# addonv2.net
KiCad netlist of a schematic drawn in EAGLE
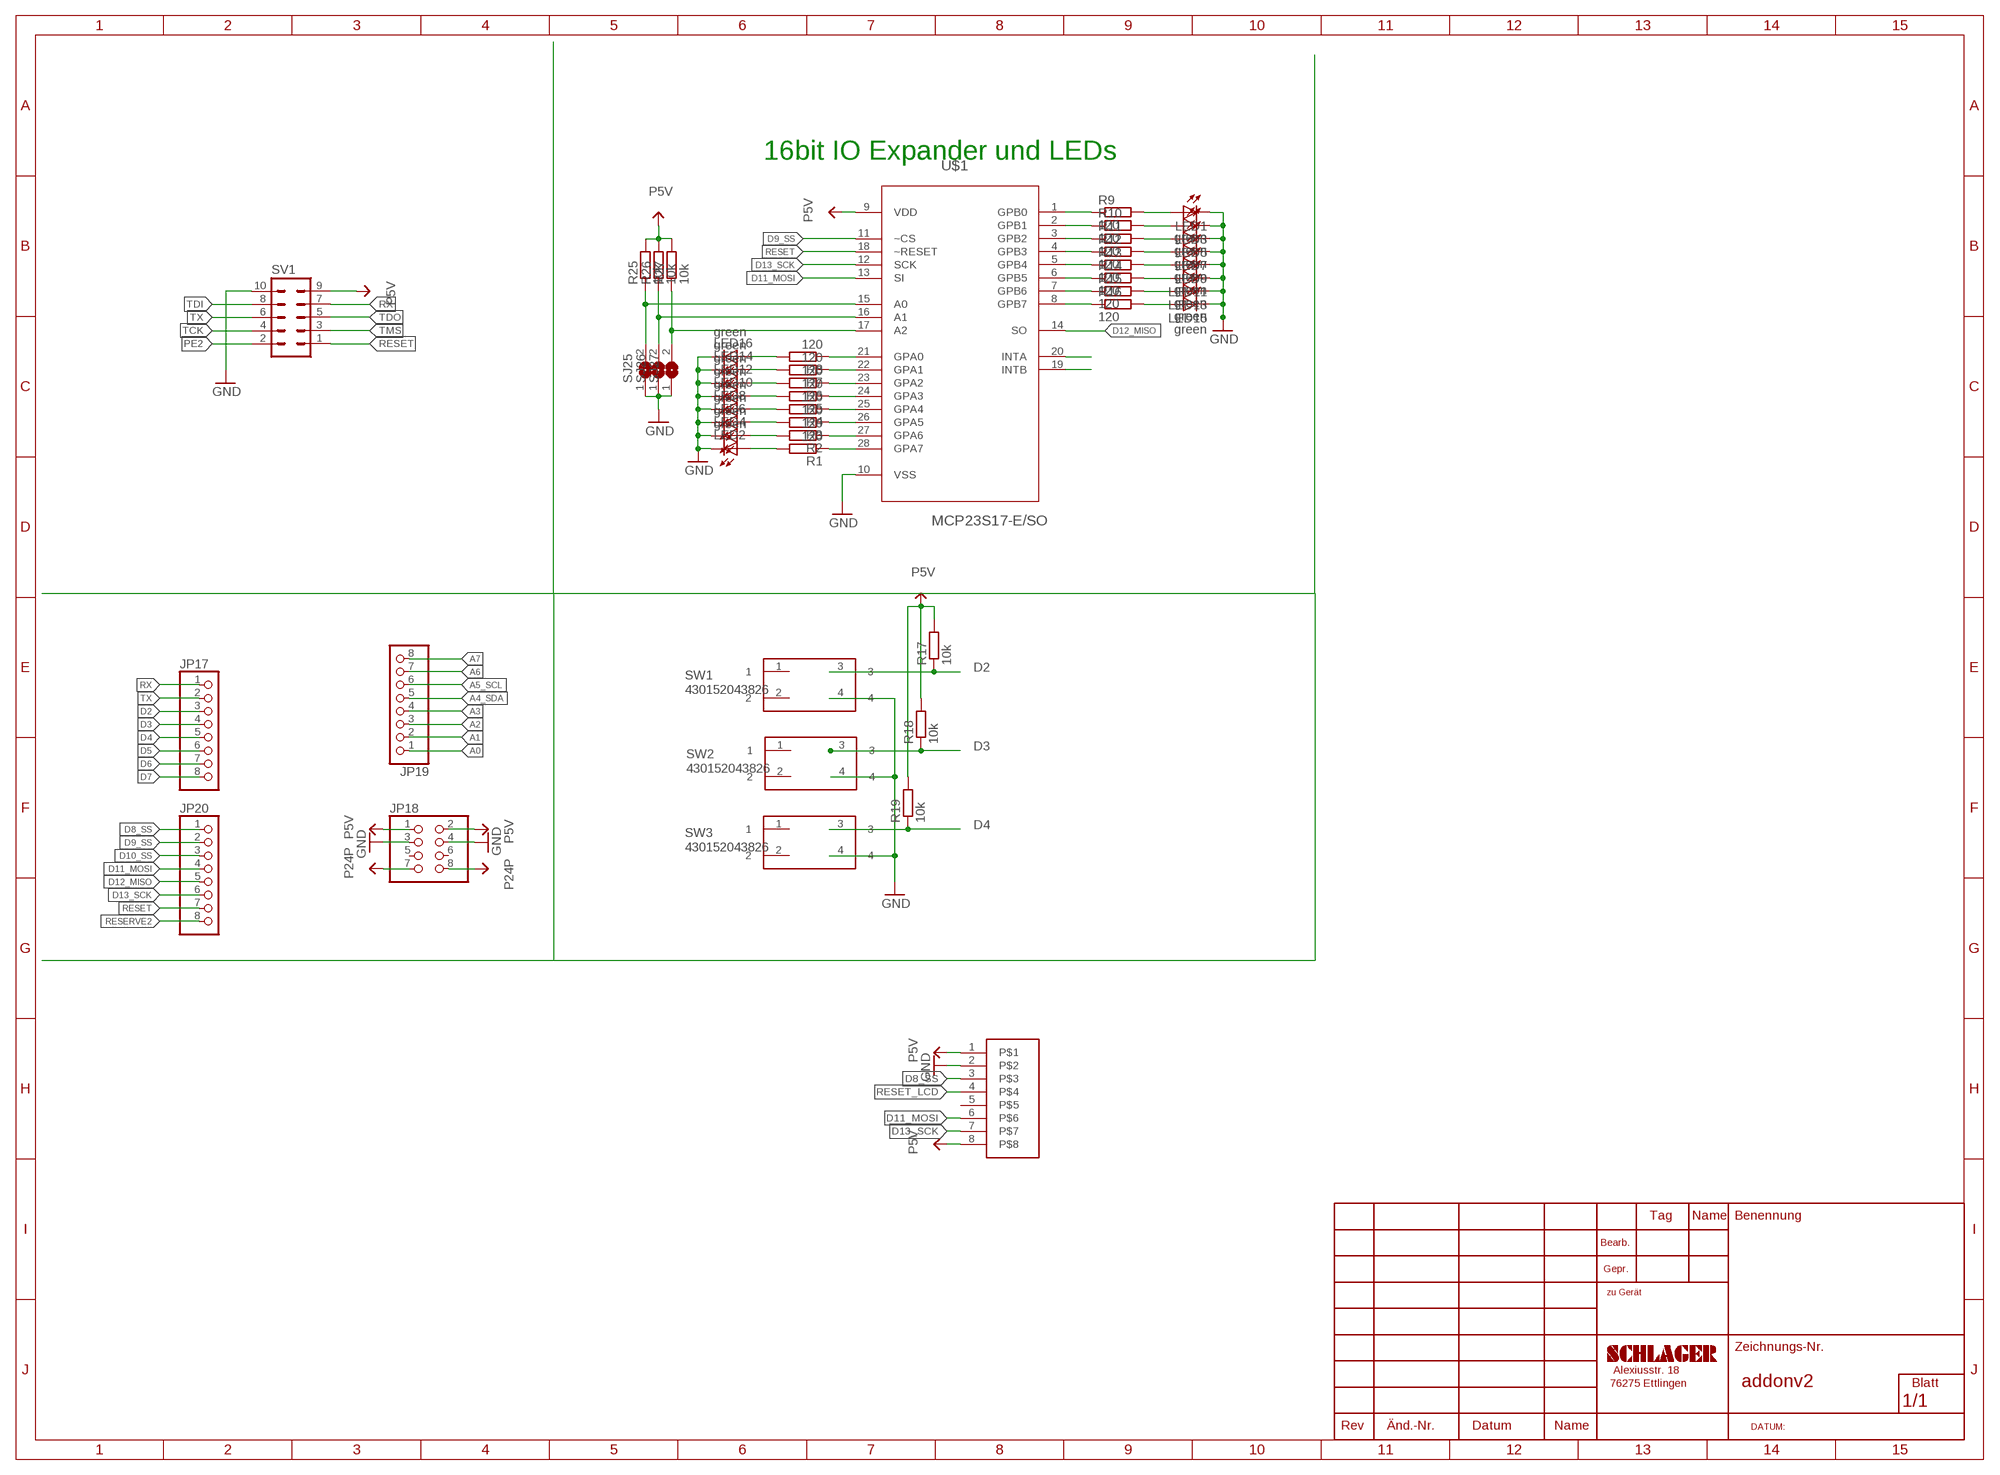
[diagram p0: schematic, sheet 1]

(export (version "E")
  (design (tool "Eeschema 10.0.6"))
  (components
    (comp (ref "JP17")
      (value "PINHD-1X8")
      (footprint "eagle-import:1X08")
      (libsource (lib "eagle-import") (part "PINHD-1X8"))
    )
    (comp (ref "JP18")
      (value "PINHD-2X4")
      (footprint "eagle-import:2X04")
      (libsource (lib "eagle-import") (part "PINHD-2X4"))
    )
    (comp (ref "JP19")
      (value "PINHD-1X8")
      (footprint "eagle-import:1X08")
      (libsource (lib "eagle-import") (part "PINHD-1X8"))
    )
    (comp (ref "JP20")
      (value "PINHD-1X8")
      (footprint "eagle-import:1X08")
      (libsource (lib "eagle-import") (part "PINHD-1X8"))
    )
    (comp (ref "LED1")
      (value "green")
      (footprint "eagle-import:CHIPLED_0805")
      (libsource (lib "eagle-import") (part "LEDCHIPLED_0805"))
    )
    (comp (ref "LED2")
      (value "green")
      (footprint "eagle-import:CHIPLED_0805")
      (libsource (lib "eagle-import") (part "LEDCHIPLED_0805"))
    )
    (comp (ref "LED3")
      (value "green")
      (footprint "eagle-import:CHIPLED_0805")
      (libsource (lib "eagle-import") (part "LEDCHIPLED_0805"))
    )
    (comp (ref "LED4")
      (value "green")
      (footprint "eagle-import:CHIPLED_0805")
      (libsource (lib "eagle-import") (part "LEDCHIPLED_0805"))
    )
    (comp (ref "LED5")
      (value "green")
      (footprint "eagle-import:CHIPLED_0805")
      (libsource (lib "eagle-import") (part "LEDCHIPLED_0805"))
    )
    (comp (ref "LED6")
      (value "green")
      (footprint "eagle-import:CHIPLED_0805")
      (libsource (lib "eagle-import") (part "LEDCHIPLED_0805"))
    )
    (comp (ref "LED7")
      (value "green")
      (footprint "eagle-import:CHIPLED_0805")
      (libsource (lib "eagle-import") (part "LEDCHIPLED_0805"))
    )
    (comp (ref "LED8")
      (value "green")
      (footprint "eagle-import:CHIPLED_0805")
      (libsource (lib "eagle-import") (part "LEDCHIPLED_0805"))
    )
    (comp (ref "LED9")
      (value "green")
      (footprint "eagle-import:CHIPLED_0805")
      (libsource (lib "eagle-import") (part "LEDCHIPLED_0805"))
    )
    (comp (ref "LED10")
      (value "green")
      (footprint "eagle-import:CHIPLED_0805")
      (libsource (lib "eagle-import") (part "LEDCHIPLED_0805"))
    )
    (comp (ref "LED11")
      (value "green")
      (footprint "eagle-import:CHIPLED_0805")
      (libsource (lib "eagle-import") (part "LEDCHIPLED_0805"))
    )
    (comp (ref "LED12")
      (value "green")
      (footprint "eagle-import:CHIPLED_0805")
      (libsource (lib "eagle-import") (part "LEDCHIPLED_0805"))
    )
    (comp (ref "LED13")
      (value "green")
      (footprint "eagle-import:CHIPLED_0805")
      (libsource (lib "eagle-import") (part "LEDCHIPLED_0805"))
    )
    (comp (ref "LED14")
      (value "green")
      (footprint "eagle-import:CHIPLED_0805")
      (libsource (lib "eagle-import") (part "LEDCHIPLED_0805"))
    )
    (comp (ref "LED15")
      (value "green")
      (footprint "eagle-import:CHIPLED_0805")
      (libsource (lib "eagle-import") (part "LEDCHIPLED_0805"))
    )
    (comp (ref "LED16")
      (value "green")
      (footprint "eagle-import:CHIPLED_0805")
      (libsource (lib "eagle-import") (part "LEDCHIPLED_0805"))
    )
    (comp (ref "R1")
      (value "120")
      (footprint "eagle-import:R0805")
      (libsource (lib "eagle-import") (part "R-EU_R0805"))
    )
    (comp (ref "R2")
      (value "120")
      (footprint "eagle-import:R0805")
      (libsource (lib "eagle-import") (part "R-EU_R0805"))
    )
    (comp (ref "R3")
      (value "120")
      (footprint "eagle-import:R0805")
      (libsource (lib "eagle-import") (part "R-EU_R0805"))
    )
    (comp (ref "R4")
      (value "120")
      (footprint "eagle-import:R0805")
      (libsource (lib "eagle-import") (part "R-EU_R0805"))
    )
    (comp (ref "R5")
      (value "120")
      (footprint "eagle-import:R0805")
      (libsource (lib "eagle-import") (part "R-EU_R0805"))
    )
    (comp (ref "R6")
      (value "120")
      (footprint "eagle-import:R0805")
      (libsource (lib "eagle-import") (part "R-EU_R0805"))
    )
    (comp (ref "R7")
      (value "120")
      (footprint "eagle-import:R0805")
      (libsource (lib "eagle-import") (part "R-EU_R0805"))
    )
    (comp (ref "R8")
      (value "120")
      (footprint "eagle-import:R0805")
      (libsource (lib "eagle-import") (part "R-EU_R0805"))
    )
    (comp (ref "R9")
      (value "120")
      (footprint "eagle-import:R0805")
      (libsource (lib "eagle-import") (part "R-EU_R0805"))
    )
    (comp (ref "R10")
      (value "120")
      (footprint "eagle-import:R0805")
      (libsource (lib "eagle-import") (part "R-EU_R0805"))
    )
    (comp (ref "R11")
      (value "120")
      (footprint "eagle-import:R0805")
      (libsource (lib "eagle-import") (part "R-EU_R0805"))
    )
    (comp (ref "R12")
      (value "120")
      (footprint "eagle-import:R0805")
      (libsource (lib "eagle-import") (part "R-EU_R0805"))
    )
    (comp (ref "R13")
      (value "120")
      (footprint "eagle-import:R0805")
      (libsource (lib "eagle-import") (part "R-EU_R0805"))
    )
    (comp (ref "R14")
      (value "120")
      (footprint "eagle-import:R0805")
      (libsource (lib "eagle-import") (part "R-EU_R0805"))
    )
    (comp (ref "R15")
      (value "120")
      (footprint "eagle-import:R0805")
      (libsource (lib "eagle-import") (part "R-EU_R0805"))
    )
    (comp (ref "R16")
      (value "120")
      (footprint "eagle-import:R0805")
      (libsource (lib "eagle-import") (part "R-EU_R0805"))
    )
    (comp (ref "R17")
      (value "10k")
      (footprint "eagle-import:R0805")
      (libsource (lib "eagle-import") (part "R-EU_R0805"))
    )
    (comp (ref "R18")
      (value "10k")
      (footprint "eagle-import:R0805")
      (libsource (lib "eagle-import") (part "R-EU_R0805"))
    )
    (comp (ref "R19")
      (value "10k")
      (footprint "eagle-import:R0805")
      (libsource (lib "eagle-import") (part "R-EU_R0805"))
    )
    (comp (ref "R25")
      (value "10k")
      (footprint "eagle-import:R0805")
      (libsource (lib "eagle-import") (part "R-EU_R0805"))
    )
    (comp (ref "R26")
      (value "10k")
      (footprint "eagle-import:R0805")
      (libsource (lib "eagle-import") (part "R-EU_R0805"))
    )
    (comp (ref "R27")
      (value "10k")
      (footprint "eagle-import:R0805")
      (libsource (lib "eagle-import") (part "R-EU_R0805"))
    )
    (comp (ref "SJ25")
      (value "SJN")
      (footprint "eagle-import:SJ")
      (libsource (lib "eagle-import") (part "SJN"))
    )
    (comp (ref "SJ26")
      (value "SJN")
      (footprint "eagle-import:SJ")
      (libsource (lib "eagle-import") (part "SJN"))
    )
    (comp (ref "SJ27")
      (value "SJN")
      (footprint "eagle-import:SJ")
      (libsource (lib "eagle-import") (part "SJN"))
    )
    (comp (ref "SV1")
      (value "ML10L")
      (footprint "eagle-import:ML10L")
      (libsource (lib "eagle-import") (part "ML10L"))
    )
    (comp (ref "SW1")
      (value "430152043826")
      (footprint "eagle-import:430152043826")
      (libsource (lib "eagle-import") (part "430152043826"))
    )
    (comp (ref "SW2")
      (value "430152043826")
      (footprint "eagle-import:430152043826")
      (libsource (lib "eagle-import") (part "430152043826"))
    )
    (comp (ref "SW3")
      (value "430152043826")
      (footprint "eagle-import:430152043826")
      (libsource (lib "eagle-import") (part "430152043826"))
    )
    (comp (ref "U$1")
      (value "MCP23S17-E/SO")
      (footprint "eagle-import:SOIC127P030X265-28N")
      (libsource (lib "eagle-import") (part "MCP23S17-E/SO"))
    )
    (comp (ref "U$3")
      (value "1.44-128X128")
      (footprint "eagle-import:1.44-128X128")
      (libsource (lib "eagle-import") (part "1.44-128X128"))
    )
  )
  (nets
    (net (code "1") (name "A0") (class "Default")
      (node (ref "JP19") (pin "1") (pinfunction "1_1") (pintype "passive"))
    )
    (net (code "2") (name "A1") (class "Default")
      (node (ref "JP19") (pin "2") (pinfunction "2_2") (pintype "passive"))
    )
    (net (code "3") (name "A2") (class "Default")
      (node (ref "JP19") (pin "3") (pinfunction "3_3") (pintype "passive"))
    )
    (net (code "4") (name "A3") (class "Default")
      (node (ref "JP19") (pin "4") (pinfunction "4_4") (pintype "passive"))
    )
    (net (code "5") (name "A4_SDA") (class "Default")
      (node (ref "JP19") (pin "5") (pinfunction "5_5") (pintype "passive"))
    )
    (net (code "6") (name "A5_SCL") (class "Default")
      (node (ref "JP19") (pin "6") (pinfunction "6_6") (pintype "passive"))
    )
    (net (code "7") (name "A6") (class "Default")
      (node (ref "JP19") (pin "7") (pinfunction "7_7") (pintype "passive"))
    )
    (net (code "8") (name "A7") (class "Default")
      (node (ref "JP19") (pin "8") (pinfunction "8_8") (pintype "passive"))
    )
    (net (code "9") (name "D2") (class "Default")
      (node (ref "JP17") (pin "3") (pinfunction "3_3") (pintype "passive"))
      (node (ref "R17") (pin "1") (pinfunction "1_1") (pintype "passive"))
      (node (ref "SW1") (pin "3") (pinfunction "3_3") (pintype "bidirectional"))
    )
    (net (code "10") (name "D3") (class "Default")
      (node (ref "JP17") (pin "4") (pinfunction "4_4") (pintype "passive"))
      (node (ref "R18") (pin "1") (pinfunction "1_1") (pintype "passive"))
      (node (ref "SW2") (pin "3") (pinfunction "3_3") (pintype "bidirectional"))
    )
    (net (code "11") (name "D4") (class "Default")
      (node (ref "JP17") (pin "5") (pinfunction "5_5") (pintype "passive"))
      (node (ref "R19") (pin "1") (pinfunction "1_1") (pintype "passive"))
      (node (ref "SW3") (pin "3") (pinfunction "3_3") (pintype "bidirectional"))
    )
    (net (code "12") (name "D5") (class "Default")
      (node (ref "JP17") (pin "6") (pinfunction "6_6") (pintype "passive"))
    )
    (net (code "13") (name "D6") (class "Default")
      (node (ref "JP17") (pin "7") (pinfunction "7_7") (pintype "passive"))
    )
    (net (code "14") (name "D7") (class "Default")
      (node (ref "JP17") (pin "8") (pinfunction "8_8") (pintype "passive"))
    )
    (net (code "15") (name "D8_SS") (class "Default")
      (node (ref "JP20") (pin "1") (pinfunction "1_1") (pintype "passive"))
      (node (ref "U$3") (pin "3") (pinfunction "P$3_3") (pintype "bidirectional"))
    )
    (net (code "16") (name "D9_SS") (class "Default")
      (node (ref "JP20") (pin "2") (pinfunction "2_2") (pintype "passive"))
      (node (ref "U$1") (pin "11") (pinfunction "~{CS}_11") (pintype "input"))
    )
    (net (code "17") (name "D10_SS") (class "Default")
      (node (ref "JP20") (pin "3") (pinfunction "3_3") (pintype "passive"))
    )
    (net (code "18") (name "D11_MOSI") (class "Default")
      (node (ref "JP20") (pin "4") (pinfunction "4_4") (pintype "passive"))
      (node (ref "U$1") (pin "13") (pinfunction "SI_13") (pintype "input"))
      (node (ref "U$3") (pin "6") (pinfunction "P$6_6") (pintype "bidirectional"))
    )
    (net (code "19") (name "D12_MISO") (class "Default")
      (node (ref "JP20") (pin "5") (pinfunction "5_5") (pintype "passive"))
      (node (ref "U$1") (pin "14") (pinfunction "SO_14") (pintype "output"))
    )
    (net (code "20") (name "D13_SCK") (class "Default")
      (node (ref "JP20") (pin "6") (pinfunction "6_6") (pintype "passive"))
      (node (ref "U$1") (pin "12") (pinfunction "SCK_12") (pintype "input"))
      (node (ref "U$3") (pin "7") (pinfunction "P$7_7") (pintype "bidirectional"))
    )
    (net (code "21") (name "GND") (class "Default")
      (node (ref "JP18") (pin "3") (pinfunction "3_3") (pintype "passive"))
      (node (ref "JP18") (pin "4") (pinfunction "4_4") (pintype "passive"))
      (node (ref "LED1") (pin "C") (pinfunction "C_C") (pintype "passive"))
      (node (ref "LED10") (pin "C") (pinfunction "C_C") (pintype "passive"))
      (node (ref "LED11") (pin "C") (pinfunction "C_C") (pintype "passive"))
      (node (ref "LED12") (pin "C") (pinfunction "C_C") (pintype "passive"))
      (node (ref "LED13") (pin "C") (pinfunction "C_C") (pintype "passive"))
      (node (ref "LED14") (pin "C") (pinfunction "C_C") (pintype "passive"))
      (node (ref "LED15") (pin "C") (pinfunction "C_C") (pintype "passive"))
      (node (ref "LED16") (pin "C") (pinfunction "C_C") (pintype "passive"))
      (node (ref "LED2") (pin "C") (pinfunction "C_C") (pintype "passive"))
      (node (ref "LED3") (pin "C") (pinfunction "C_C") (pintype "passive"))
      (node (ref "LED4") (pin "C") (pinfunction "C_C") (pintype "passive"))
      (node (ref "LED5") (pin "C") (pinfunction "C_C") (pintype "passive"))
      (node (ref "LED6") (pin "C") (pinfunction "C_C") (pintype "passive"))
      (node (ref "LED7") (pin "C") (pinfunction "C_C") (pintype "passive"))
      (node (ref "LED8") (pin "C") (pinfunction "C_C") (pintype "passive"))
      (node (ref "LED9") (pin "C") (pinfunction "C_C") (pintype "passive"))
      (node (ref "SJ25") (pin "1") (pinfunction "1_1") (pintype "passive"))
      (node (ref "SJ26") (pin "1") (pinfunction "1_1") (pintype "passive"))
      (node (ref "SJ27") (pin "1") (pinfunction "1_1") (pintype "passive"))
      (node (ref "SV1") (pin "10") (pinfunction "10_10") (pintype "passive"))
      (node (ref "SW1") (pin "4") (pinfunction "4_4") (pintype "bidirectional"))
      (node (ref "SW2") (pin "4") (pinfunction "4_4") (pintype "bidirectional"))
      (node (ref "SW3") (pin "4") (pinfunction "4_4") (pintype "bidirectional"))
      (node (ref "U$1") (pin "10") (pinfunction "VSS_10") (pintype "power_in"))
      (node (ref "U$3") (pin "2") (pinfunction "P$2_2") (pintype "bidirectional"))
    )
    (net (code "22") (name "Net-(LED1-PadA)") (class "Default")
      (node (ref "LED1") (pin "A") (pinfunction "A_A") (pintype "passive"))
      (node (ref "R9") (pin "2") (pinfunction "2_2") (pintype "passive"))
    )
    (net (code "23") (name "Net-(LED2-PadA)") (class "Default")
      (node (ref "LED2") (pin "A") (pinfunction "A_A") (pintype "passive"))
      (node (ref "R1") (pin "2") (pinfunction "2_2") (pintype "passive"))
    )
    (net (code "24") (name "Net-(LED3-PadA)") (class "Default")
      (node (ref "LED3") (pin "A") (pinfunction "A_A") (pintype "passive"))
      (node (ref "R10") (pin "2") (pinfunction "2_2") (pintype "passive"))
    )
    (net (code "25") (name "Net-(LED4-PadA)") (class "Default")
      (node (ref "LED4") (pin "A") (pinfunction "A_A") (pintype "passive"))
      (node (ref "R2") (pin "2") (pinfunction "2_2") (pintype "passive"))
    )
    (net (code "26") (name "Net-(LED5-PadA)") (class "Default")
      (node (ref "LED5") (pin "A") (pinfunction "A_A") (pintype "passive"))
      (node (ref "R11") (pin "2") (pinfunction "2_2") (pintype "passive"))
    )
    (net (code "27") (name "Net-(LED6-PadA)") (class "Default")
      (node (ref "LED6") (pin "A") (pinfunction "A_A") (pintype "passive"))
      (node (ref "R3") (pin "2") (pinfunction "2_2") (pintype "passive"))
    )
    (net (code "28") (name "Net-(LED7-PadA)") (class "Default")
      (node (ref "LED7") (pin "A") (pinfunction "A_A") (pintype "passive"))
      (node (ref "R12") (pin "2") (pinfunction "2_2") (pintype "passive"))
    )
    (net (code "29") (name "Net-(LED8-PadA)") (class "Default")
      (node (ref "LED8") (pin "A") (pinfunction "A_A") (pintype "passive"))
      (node (ref "R4") (pin "2") (pinfunction "2_2") (pintype "passive"))
    )
    (net (code "30") (name "Net-(LED9-PadA)") (class "Default")
      (node (ref "LED9") (pin "A") (pinfunction "A_A") (pintype "passive"))
      (node (ref "R13") (pin "2") (pinfunction "2_2") (pintype "passive"))
    )
    (net (code "31") (name "Net-(LED10-PadA)") (class "Default")
      (node (ref "LED10") (pin "A") (pinfunction "A_A") (pintype "passive"))
      (node (ref "R5") (pin "2") (pinfunction "2_2") (pintype "passive"))
    )
    (net (code "32") (name "Net-(LED11-PadA)") (class "Default")
      (node (ref "LED11") (pin "A") (pinfunction "A_A") (pintype "passive"))
      (node (ref "R14") (pin "2") (pinfunction "2_2") (pintype "passive"))
    )
    (net (code "33") (name "Net-(LED12-PadA)") (class "Default")
      (node (ref "LED12") (pin "A") (pinfunction "A_A") (pintype "passive"))
      (node (ref "R6") (pin "2") (pinfunction "2_2") (pintype "passive"))
    )
    (net (code "34") (name "Net-(LED13-PadA)") (class "Default")
      (node (ref "LED13") (pin "A") (pinfunction "A_A") (pintype "passive"))
      (node (ref "R15") (pin "2") (pinfunction "2_2") (pintype "passive"))
    )
    (net (code "35") (name "Net-(LED14-PadA)") (class "Default")
      (node (ref "LED14") (pin "A") (pinfunction "A_A") (pintype "passive"))
      (node (ref "R7") (pin "2") (pinfunction "2_2") (pintype "passive"))
    )
    (net (code "36") (name "Net-(LED15-PadA)") (class "Default")
      (node (ref "LED15") (pin "A") (pinfunction "A_A") (pintype "passive"))
      (node (ref "R16") (pin "2") (pinfunction "2_2") (pintype "passive"))
    )
    (net (code "37") (name "Net-(LED16-PadA)") (class "Default")
      (node (ref "LED16") (pin "A") (pinfunction "A_A") (pintype "passive"))
      (node (ref "R8") (pin "2") (pinfunction "2_2") (pintype "passive"))
    )
    (net (code "38") (name "Net-(U$1-A0)") (class "Default")
      (node (ref "R25") (pin "1") (pinfunction "1_1") (pintype "passive"))
      (node (ref "SJ25") (pin "2") (pinfunction "2_2") (pintype "passive"))
      (node (ref "U$1") (pin "15") (pinfunction "A0_15") (pintype "input"))
    )
    (net (code "39") (name "Net-(U$1-A1)") (class "Default")
      (node (ref "R26") (pin "1") (pinfunction "1_1") (pintype "passive"))
      (node (ref "SJ26") (pin "2") (pinfunction "2_2") (pintype "passive"))
      (node (ref "U$1") (pin "16") (pinfunction "A1_16") (pintype "input"))
    )
    (net (code "40") (name "Net-(U$1-A2)") (class "Default")
      (node (ref "R27") (pin "1") (pinfunction "1_1") (pintype "passive"))
      (node (ref "SJ27") (pin "2") (pinfunction "2_2") (pintype "passive"))
      (node (ref "U$1") (pin "17") (pinfunction "A2_17") (pintype "input"))
    )
    (net (code "41") (name "Net-(U$1-GPA0)") (class "Default")
      (node (ref "R8") (pin "1") (pinfunction "1_1") (pintype "passive"))
      (node (ref "U$1") (pin "21") (pinfunction "GPA0_21") (pintype "bidirectional"))
    )
    (net (code "42") (name "Net-(U$1-GPA1)") (class "Default")
      (node (ref "R7") (pin "1") (pinfunction "1_1") (pintype "passive"))
      (node (ref "U$1") (pin "22") (pinfunction "GPA1_22") (pintype "bidirectional"))
    )
    (net (code "43") (name "Net-(U$1-GPA2)") (class "Default")
      (node (ref "R6") (pin "1") (pinfunction "1_1") (pintype "passive"))
      (node (ref "U$1") (pin "23") (pinfunction "GPA2_23") (pintype "bidirectional"))
    )
    (net (code "44") (name "Net-(U$1-GPA3)") (class "Default")
      (node (ref "R5") (pin "1") (pinfunction "1_1") (pintype "passive"))
      (node (ref "U$1") (pin "24") (pinfunction "GPA3_24") (pintype "bidirectional"))
    )
    (net (code "45") (name "Net-(U$1-GPA4)") (class "Default")
      (node (ref "R4") (pin "1") (pinfunction "1_1") (pintype "passive"))
      (node (ref "U$1") (pin "25") (pinfunction "GPA4_25") (pintype "bidirectional"))
    )
    (net (code "46") (name "Net-(U$1-GPA5)") (class "Default")
      (node (ref "R3") (pin "1") (pinfunction "1_1") (pintype "passive"))
      (node (ref "U$1") (pin "26") (pinfunction "GPA5_26") (pintype "bidirectional"))
    )
    (net (code "47") (name "Net-(U$1-GPA6)") (class "Default")
      (node (ref "R2") (pin "1") (pinfunction "1_1") (pintype "passive"))
      (node (ref "U$1") (pin "27") (pinfunction "GPA6_27") (pintype "bidirectional"))
    )
    (net (code "48") (name "Net-(U$1-GPA7)") (class "Default")
      (node (ref "R1") (pin "1") (pinfunction "1_1") (pintype "passive"))
      (node (ref "U$1") (pin "28") (pinfunction "GPA7_28") (pintype "bidirectional"))
    )
    (net (code "49") (name "Net-(U$1-GPB0)") (class "Default")
      (node (ref "R9") (pin "1") (pinfunction "1_1") (pintype "passive"))
      (node (ref "U$1") (pin "1") (pinfunction "GPB0_1") (pintype "bidirectional"))
    )
    (net (code "50") (name "Net-(U$1-GPB1)") (class "Default")
      (node (ref "R10") (pin "1") (pinfunction "1_1") (pintype "passive"))
      (node (ref "U$1") (pin "2") (pinfunction "GPB1_2") (pintype "bidirectional"))
    )
    (net (code "51") (name "Net-(U$1-GPB2)") (class "Default")
      (node (ref "R11") (pin "1") (pinfunction "1_1") (pintype "passive"))
      (node (ref "U$1") (pin "3") (pinfunction "GPB2_3") (pintype "bidirectional"))
    )
    (net (code "52") (name "Net-(U$1-GPB3)") (class "Default")
      (node (ref "R12") (pin "1") (pinfunction "1_1") (pintype "passive"))
      (node (ref "U$1") (pin "4") (pinfunction "GPB3_4") (pintype "bidirectional"))
    )
    (net (code "53") (name "Net-(U$1-GPB4)") (class "Default")
      (node (ref "R13") (pin "1") (pinfunction "1_1") (pintype "passive"))
      (node (ref "U$1") (pin "5") (pinfunction "GPB4_5") (pintype "bidirectional"))
    )
    (net (code "54") (name "Net-(U$1-GPB5)") (class "Default")
      (node (ref "R14") (pin "1") (pinfunction "1_1") (pintype "passive"))
      (node (ref "U$1") (pin "6") (pinfunction "GPB5_6") (pintype "bidirectional"))
    )
    (net (code "55") (name "Net-(U$1-GPB6)") (class "Default")
      (node (ref "R15") (pin "1") (pinfunction "1_1") (pintype "passive"))
      (node (ref "U$1") (pin "7") (pinfunction "GPB6_7") (pintype "bidirectional"))
    )
    (net (code "56") (name "Net-(U$1-GPB7)") (class "Default")
      (node (ref "R16") (pin "1") (pinfunction "1_1") (pintype "passive"))
      (node (ref "U$1") (pin "8") (pinfunction "GPB7_8") (pintype "bidirectional"))
    )
    (net (code "57") (name "P5V") (class "Default")
      (node (ref "JP18") (pin "1") (pinfunction "1_1") (pintype "passive"))
      (node (ref "JP18") (pin "2") (pinfunction "2_2") (pintype "passive"))
      (node (ref "R17") (pin "2") (pinfunction "2_2") (pintype "passive"))
      (node (ref "R18") (pin "2") (pinfunction "2_2") (pintype "passive"))
      (node (ref "R19") (pin "2") (pinfunction "2_2") (pintype "passive"))
      (node (ref "R25") (pin "2") (pinfunction "2_2") (pintype "passive"))
      (node (ref "R26") (pin "2") (pinfunction "2_2") (pintype "passive"))
      (node (ref "R27") (pin "2") (pinfunction "2_2") (pintype "passive"))
      (node (ref "SV1") (pin "9") (pinfunction "9_9") (pintype "passive"))
      (node (ref "U$1") (pin "9") (pinfunction "VDD_9") (pintype "power_in"))
      (node (ref "U$3") (pin "1") (pinfunction "P$1_1") (pintype "bidirectional"))
      (node (ref "U$3") (pin "8") (pinfunction "P$8_8") (pintype "bidirectional"))
    )
    (net (code "58") (name "P24P") (class "Default")
      (node (ref "JP18") (pin "7") (pinfunction "7_7") (pintype "passive"))
      (node (ref "JP18") (pin "8") (pinfunction "8_8") (pintype "passive"))
    )
    (net (code "59") (name "PE2") (class "Default")
      (node (ref "SV1") (pin "2") (pinfunction "2_2") (pintype "passive"))
    )
    (net (code "60") (name "RESERVE2") (class "Default")
      (node (ref "JP20") (pin "8") (pinfunction "8_8") (pintype "passive"))
    )
    (net (code "61") (name "RESET") (class "Default")
      (node (ref "JP20") (pin "7") (pinfunction "7_7") (pintype "passive"))
      (node (ref "SV1") (pin "1") (pinfunction "1_1") (pintype "passive"))
      (node (ref "U$1") (pin "18") (pinfunction "~{RESET}_18") (pintype "input"))
    )
    (net (code "62") (name "RESET_LCD") (class "Default")
      (node (ref "U$3") (pin "4") (pinfunction "P$4_4") (pintype "bidirectional"))
    )
    (net (code "63") (name "RX") (class "Default")
      (node (ref "JP17") (pin "1") (pinfunction "1_1") (pintype "passive"))
      (node (ref "SV1") (pin "7") (pinfunction "7_7") (pintype "passive"))
    )
    (net (code "64") (name "TCK") (class "Default")
      (node (ref "SV1") (pin "4") (pinfunction "4_4") (pintype "passive"))
    )
    (net (code "65") (name "TDI") (class "Default")
      (node (ref "SV1") (pin "8") (pinfunction "8_8") (pintype "passive"))
    )
    (net (code "66") (name "TDO") (class "Default")
      (node (ref "SV1") (pin "5") (pinfunction "5_5") (pintype "passive"))
    )
    (net (code "67") (name "TMS") (class "Default")
      (node (ref "SV1") (pin "3") (pinfunction "3_3") (pintype "passive"))
    )
    (net (code "68") (name "TX") (class "Default")
      (node (ref "JP17") (pin "2") (pinfunction "2_2") (pintype "passive"))
      (node (ref "SV1") (pin "6") (pinfunction "6_6") (pintype "passive"))
    )
    (net (code "69") (name "unconnected-(JP18-Pad5)") (class "Default")
      (node (ref "JP18") (pin "5") (pinfunction "5_5") (pintype "passive"))
    )
    (net (code "70") (name "unconnected-(JP18-Pad6)") (class "Default")
      (node (ref "JP18") (pin "6") (pinfunction "6_6") (pintype "passive"))
    )
    (net (code "71") (name "unconnected-(SW1-Pad1)") (class "Default")
      (node (ref "SW1") (pin "1") (pinfunction "1_1") (pintype "bidirectional"))
    )
    (net (code "72") (name "unconnected-(SW1-Pad2)") (class "Default")
      (node (ref "SW1") (pin "2") (pinfunction "2_2") (pintype "bidirectional"))
    )
    (net (code "73") (name "unconnected-(SW2-Pad1)") (class "Default")
      (node (ref "SW2") (pin "1") (pinfunction "1_1") (pintype "bidirectional"))
    )
    (net (code "74") (name "unconnected-(SW2-Pad2)") (class "Default")
      (node (ref "SW2") (pin "2") (pinfunction "2_2") (pintype "bidirectional"))
    )
    (net (code "75") (name "unconnected-(SW3-Pad1)") (class "Default")
      (node (ref "SW3") (pin "1") (pinfunction "1_1") (pintype "bidirectional"))
    )
    (net (code "76") (name "unconnected-(SW3-Pad2)") (class "Default")
      (node (ref "SW3") (pin "2") (pinfunction "2_2") (pintype "bidirectional"))
    )
    (net (code "77") (name "unconnected-(U$1-INTA-Pad20)") (class "Default")
      (node (ref "U$1") (pin "20") (pinfunction "INTA_20") (pintype "output"))
    )
    (net (code "78") (name "unconnected-(U$1-INTB-Pad19)") (class "Default")
      (node (ref "U$1") (pin "19") (pinfunction "INTB_19") (pintype "output"))
    )
    (net (code "79") (name "unconnected-(U$3-P$5-Pad5)") (class "Default")
      (node (ref "U$3") (pin "5") (pinfunction "P$5_5") (pintype "bidirectional"))
    )
  )
)
